# DIGILATL_INPUT.net
KiCad netlist of a schematic drawn in Altium Designer
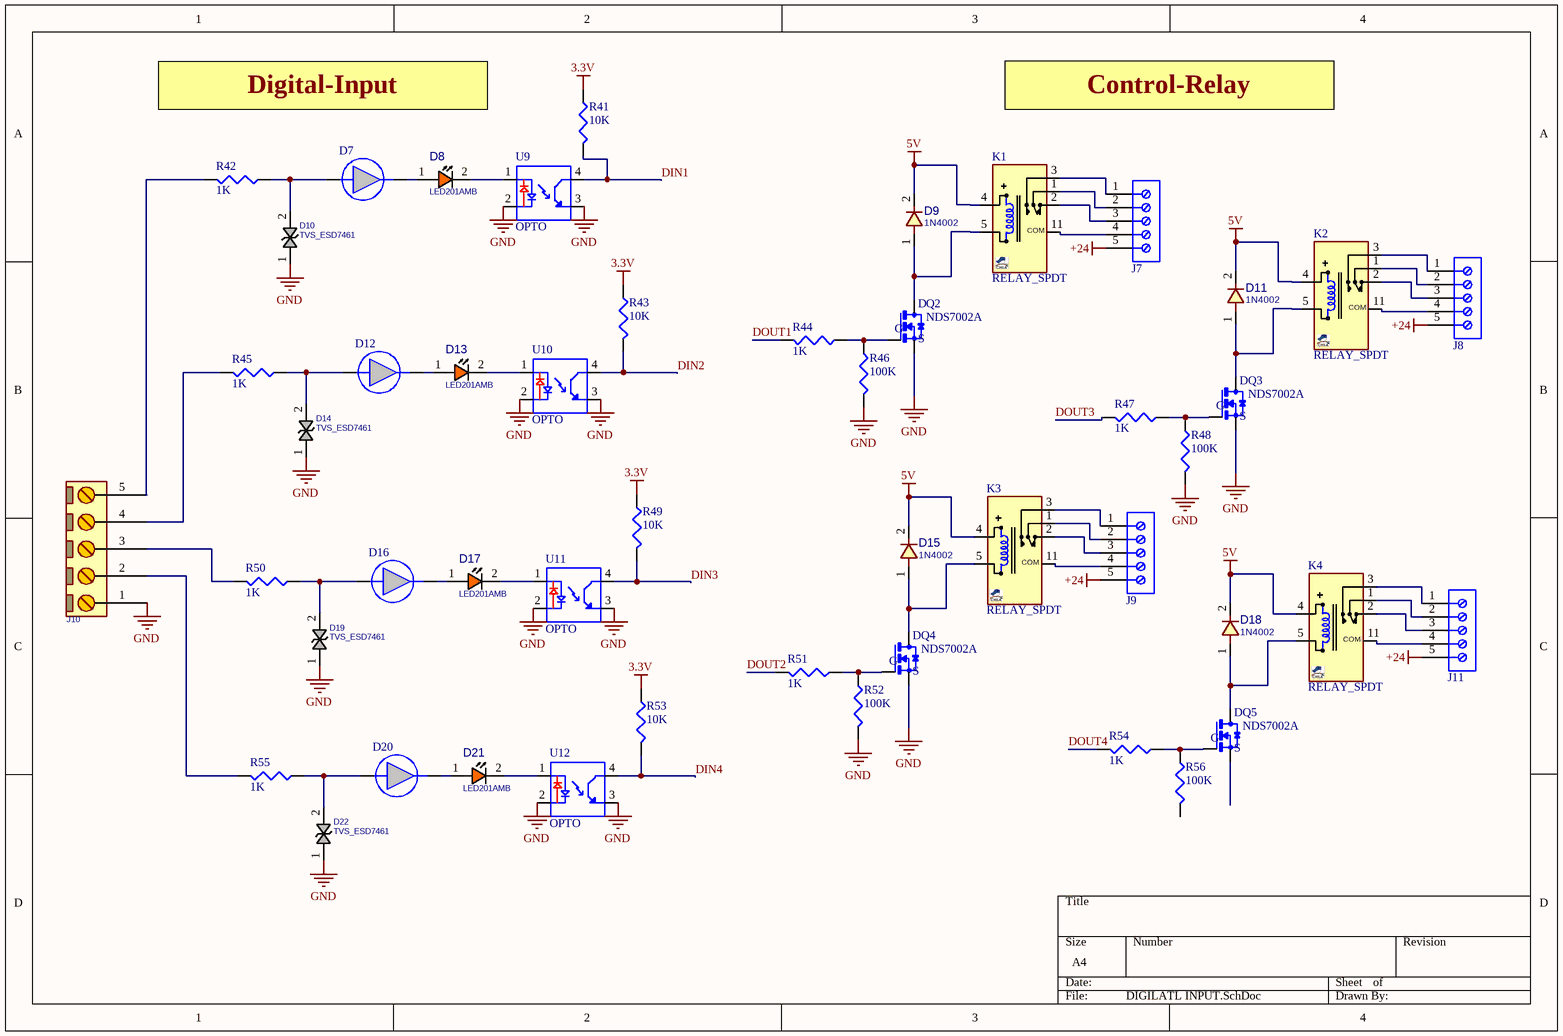
[diagram p0: DIGILATL INPUT.SchDoc]

(export (version "E")
  (design (tool "Eeschema 10.0.6"))
  (components
    (comp (ref "D7")
      (value "NSI50010YT1G")
      (footprint "DRIVER-LED")
      (description "Constant Current Regulator")
      (fields (field (name "MOUSER PART NUMBER") "863-NSI50010YT1G"))
      (libsource (lib "lib-hiony") (part "DRIVE-LED"))
    )
    (comp (ref "D8")
      (value "LED201AMB")
      (footprint "LED0201AMB")
      (description "LED, SMD, 0201, AMBER")
      (fields (field (name "MANF") "Kingbright") (field (name "MANF_P#") "APG0603SEC-TT"))
      (libsource (lib "led(diode)") (part "LED_SMD_0201_AMB"))
    )
    (comp (ref "D9")
      (value "1N4002")
      (footprint "D_SMA")
      (description "DIODE, GENERAL PURPOSE, 100V/1A")
      (fields (field (name "MANF") "MANF"))
      (libsource (lib "diode") (part "DIODE_SMD_1N4002"))
    )
    (comp (ref "D10")
      (value "TVS_ESD7461")
      (footprint "ESD_XDFN2")
      (description "TVS, ESD PROTECT, Bidirectional")
      (fields (field (name "MANF_P#") "ESD7461N2T5G") (field (name "MANF") "ON"))
      (libsource (lib "protect_tvs_esd_fuse") (part "TVS_ESD7461"))
    )
    (comp (ref "D11")
      (value "1N4002")
      (footprint "D_SMA")
      (description "DIODE, GENERAL PURPOSE, 100V/1A")
      (fields (field (name "MANF") "MANF"))
      (libsource (lib "diode") (part "DIODE_SMD_1N4002"))
    )
    (comp (ref "D12")
      (value "NSI50010YT1G")
      (footprint "DRIVER-LED")
      (description "Constant Current Regulator")
      (fields (field (name "MOUSER PART NUMBER") "863-NSI50010YT1G"))
      (libsource (lib "lib-hiony") (part "DRIVE-LED"))
    )
    (comp (ref "D13")
      (value "LED201AMB")
      (footprint "LED0201AMB")
      (description "LED, SMD, 0201, AMBER")
      (fields (field (name "MANF") "Kingbright") (field (name "MANF_P#") "APG0603SEC-TT"))
      (libsource (lib "led(diode)") (part "LED_SMD_0201_AMB"))
    )
    (comp (ref "D14")
      (value "TVS_ESD7461")
      (footprint "ESD_XDFN2")
      (description "TVS, ESD PROTECT, Bidirectional")
      (fields (field (name "MANF_P#") "ESD7461N2T5G") (field (name "MANF") "ON"))
      (libsource (lib "protect_tvs_esd_fuse") (part "TVS_ESD7461"))
    )
    (comp (ref "D15")
      (value "1N4002")
      (footprint "D_SMA")
      (description "DIODE, GENERAL PURPOSE, 100V/1A")
      (fields (field (name "MANF") "MANF"))
      (libsource (lib "diode") (part "DIODE_SMD_1N4002"))
    )
    (comp (ref "D16")
      (value "NSI50010YT1G")
      (footprint "DRIVER-LED")
      (description "Constant Current Regulator")
      (fields (field (name "MOUSER PART NUMBER") "863-NSI50010YT1G"))
      (libsource (lib "lib-hiony") (part "DRIVE-LED"))
    )
    (comp (ref "D17")
      (value "LED201AMB")
      (footprint "LED0201AMB")
      (description "LED, SMD, 0201, AMBER")
      (fields (field (name "MANF") "Kingbright") (field (name "MANF_P#") "APG0603SEC-TT"))
      (libsource (lib "led(diode)") (part "LED_SMD_0201_AMB"))
    )
    (comp (ref "D18")
      (value "1N4002")
      (footprint "D_SMA")
      (description "DIODE, GENERAL PURPOSE, 100V/1A")
      (fields (field (name "MANF") "MANF"))
      (libsource (lib "diode") (part "DIODE_SMD_1N4002"))
    )
    (comp (ref "D19")
      (value "TVS_ESD7461")
      (footprint "ESD_XDFN2")
      (description "TVS, ESD PROTECT, Bidirectional")
      (fields (field (name "MANF_P#") "ESD7461N2T5G") (field (name "MANF") "ON"))
      (libsource (lib "protect_tvs_esd_fuse") (part "TVS_ESD7461"))
    )
    (comp (ref "D20")
      (value "NSI50010YT1G")
      (footprint "DRIVER-LED")
      (description "Constant Current Regulator")
      (fields (field (name "MOUSER PART NUMBER") "863-NSI50010YT1G"))
      (libsource (lib "lib-hiony") (part "DRIVE-LED"))
    )
    (comp (ref "D21")
      (value "LED201AMB")
      (footprint "LED0201AMB")
      (description "LED, SMD, 0201, AMBER")
      (fields (field (name "MANF") "Kingbright") (field (name "MANF_P#") "APG0603SEC-TT"))
      (libsource (lib "led(diode)") (part "LED_SMD_0201_AMB"))
    )
    (comp (ref "D22")
      (value "TVS_ESD7461")
      (footprint "ESD_XDFN2")
      (description "TVS, ESD PROTECT, Bidirectional")
      (fields (field (name "MANF_P#") "ESD7461N2T5G") (field (name "MANF") "ON"))
      (libsource (lib "protect_tvs_esd_fuse") (part "TVS_ESD7461"))
    )
    (comp (ref "J7")
      (value "691137710005")
      (footprint "CONN-RELAY")
      (description "WR-TBL Series 1377 Horizontal Entry, THT, pitch 5mm, 5p")
      (fields (field (name "MANUFACTURER") "Wurth Elektronik"))
      (libsource (lib "") (part "CONN-RELAY_1"))
    )
    (comp (ref "J8")
      (value "691137710005")
      (footprint "CONN-RELAY")
      (description "WR-TBL Series 1377 Horizontal Entry, THT, pitch 5mm, 5p")
      (fields (field (name "MANUFACTURER") "Wurth Elektronik"))
      (libsource (lib "lib-hiony") (part "CONN-RELAY"))
    )
    (comp (ref "J9")
      (value "691137710005")
      (footprint "CONN-RELAY")
      (description "WR-TBL Series 1377 Horizontal Entry, THT, pitch 5mm, 5p")
      (fields (field (name "MANUFACTURER") "Wurth Elektronik"))
      (libsource (lib "") (part "CONN-RELAY_1"))
    )
    (comp (ref "J10")
      (value "CONN_TB5")
      (footprint "MSTB_5")
      (description "CONN, PHOENIX MSTB, 5-G, 5.08mm pitch")
      (libsource (lib "conn_power_terminalB") (part "CONN_MSTB_5"))
    )
    (comp (ref "J11")
      (value "691137710005")
      (footprint "CONN-RELAY")
      (description "WR-TBL Series 1377 Horizontal Entry, THT, pitch 5mm, 5p")
      (fields (field (name "MANUFACTURER") "Wurth Elektronik"))
      (libsource (lib "lib-hiony") (part "CONN-RELAY"))
    )
    (comp (ref "K1")
      (value "RELAY_SPDT")
      (footprint "REL_SPDT_6_1611")
      (description "Relay, SPDT, 5P, 15.5X11mm, TRB 125VAC/1A")
      (fields (field (name "MANF") "TTI") (field (name "MANF_P#") "TRB-12VDC-A"))
      (libsource (lib "relay") (part "RELAY_SPDT_6_1611_TRB"))
    )
    (comp (ref "K2")
      (value "RELAY_SPDT")
      (footprint "REL_SPDT_6_1611")
      (description "Relay, SPDT, 5P, 15.5X11mm, TRB 125VAC/1A")
      (fields (field (name "MANF") "TTI") (field (name "MANF_P#") "TRB-12VDC-A"))
      (libsource (lib "relay") (part "RELAY_SPDT_6_1611_TRB"))
    )
    (comp (ref "K3")
      (value "RELAY_SPDT")
      (footprint "REL_SPDT_6_1611")
      (description "Relay, SPDT, 5P, 15.5X11mm, TRB 125VAC/1A")
      (fields (field (name "MANF") "TTI") (field (name "MANF_P#") "TRB-12VDC-A"))
      (libsource (lib "relay") (part "RELAY_SPDT_6_1611_TRB"))
    )
    (comp (ref "K4")
      (value "RELAY_SPDT")
      (footprint "REL_SPDT_6_1611")
      (description "Relay, SPDT, 5P, 15.5X11mm, TRB 125VAC/1A")
      (fields (field (name "MANF") "TTI") (field (name "MANF_P#") "TRB-12VDC-A"))
      (libsource (lib "relay") (part "RELAY_SPDT_6_1611_TRB"))
    )
    (comp (ref "Q2")
      (value "NDS7002A")
      (footprint "SOT23")
      (description "NDS Series N-Channel 60 V 2 Ohm Enhancement Mode Field Effect Transistor SOT-23")
      (fields (field (name "MF") "ON Semiconductor"))
      (libsource (lib "lib-hiony") (part "NDS7002A"))
    )
    (comp (ref "Q3")
      (value "NDS7002A")
      (footprint "SOT23")
      (description "NDS Series N-Channel 60 V 2 Ohm Enhancement Mode Field Effect Transistor SOT-23")
      (fields (field (name "MF") "ON Semiconductor"))
      (libsource (lib "lib-hiony") (part "NDS7002A"))
    )
    (comp (ref "Q4")
      (value "NDS7002A")
      (footprint "SOT23")
      (description "NDS Series N-Channel 60 V 2 Ohm Enhancement Mode Field Effect Transistor SOT-23")
      (fields (field (name "MF") "ON Semiconductor"))
      (libsource (lib "lib-hiony") (part "NDS7002A"))
    )
    (comp (ref "Q5")
      (value "NDS7002A")
      (footprint "SOT23")
      (description "NDS Series N-Channel 60 V 2 Ohm Enhancement Mode Field Effect Transistor SOT-23")
      (fields (field (name "MF") "ON Semiconductor"))
      (libsource (lib "lib-hiony") (part "NDS7002A"))
    )
    (comp (ref "R41")
      (value "10K")
      (footprint "0603L")
      (description "RES SMD 10K OHM 1% 1/10W 0603")
      (fields
        (field (name "DIGI-KEY PART NUMBER") "1276-3485-1-ND")
        (field (name "MANUFACTURER PART NUMBER") "RC1608F103CS")
      )
      (libsource (lib "Miscellaneous Devices") (part "Res3"))
    )
    (comp (ref "R42")
      (value "1K")
      (footprint "0603L")
      (description "RES SMD 1K OHM 1% 1/10W 0603")
      (fields
        (field (name "DIGI-KEY PART NUMBER") "1276-3484-1-ND")
        (field (name "MANUFACTURER PART NUMBER") "RC1608F102CS")
        (field (name "PUBLISHER") "Altium Limited")
      )
      (libsource (lib "Miscellaneous Devices") (part "Res3"))
    )
    (comp (ref "R43")
      (value "10K")
      (footprint "0603L")
      (description "RES SMD 10K OHM 1% 1/10W 0603")
      (fields
        (field (name "DIGI-KEY PART NUMBER") "1276-3485-1-ND")
        (field (name "MANUFACTURER PART NUMBER") "RC1608F103CS")
      )
      (libsource (lib "Miscellaneous Devices") (part "Res3"))
    )
    (comp (ref "R44")
      (value "1K")
      (footprint "0603L")
      (description "RES SMD 1K OHM 1% 1/10W 0603")
      (fields
        (field (name "DIGI-KEY PART NUMBER") "1276-3484-1-ND")
        (field (name "MANUFACTURER PART NUMBER") "RC1608F102CS")
        (field (name "PUBLISHER") "Altium Limited")
      )
      (libsource (lib "Miscellaneous Devices") (part "Res3"))
    )
    (comp (ref "R45")
      (value "1K")
      (footprint "0603L")
      (description "RES SMD 1K OHM 1% 1/10W 0603")
      (fields
        (field (name "DIGI-KEY PART NUMBER") "1276-3484-1-ND")
        (field (name "MANUFACTURER PART NUMBER") "RC1608F102CS")
        (field (name "PUBLISHER") "Altium Limited")
      )
      (libsource (lib "Miscellaneous Devices") (part "Res3"))
    )
    (comp (ref "R46")
      (value "100K")
      (footprint "0603L")
      (description "RES SMD 1K OHM 1% 1/10W 0603")
      (fields
        (field (name "DIGI-KEY PART NUMBER") "1276-3484-1-ND")
        (field (name "MANUFACTURER PART NUMBER") "RC1608F102CS")
        (field (name "PUBLISHER") "Altium Limited")
      )
      (libsource (lib "Miscellaneous Devices") (part "Res3"))
    )
    (comp (ref "R47")
      (value "1K")
      (footprint "0603L")
      (description "RES SMD 1K OHM 1% 1/10W 0603")
      (fields
        (field (name "DIGI-KEY PART NUMBER") "1276-3484-1-ND")
        (field (name "MANUFACTURER PART NUMBER") "RC1608F102CS")
        (field (name "PUBLISHER") "Altium Limited")
      )
      (libsource (lib "Miscellaneous Devices") (part "Res3"))
    )
    (comp (ref "R48")
      (value "100K")
      (footprint "0603L")
      (description "RES SMD 1K OHM 1% 1/10W 0603")
      (fields
        (field (name "DIGI-KEY PART NUMBER") "1276-3484-1-ND")
        (field (name "MANUFACTURER PART NUMBER") "RC1608F102CS")
        (field (name "PUBLISHER") "Altium Limited")
      )
      (libsource (lib "Miscellaneous Devices") (part "Res3"))
    )
    (comp (ref "R49")
      (value "10K")
      (footprint "0603L")
      (description "RES SMD 10K OHM 1% 1/10W 0603")
      (fields
        (field (name "DIGI-KEY PART NUMBER") "1276-3485-1-ND")
        (field (name "MANUFACTURER PART NUMBER") "RC1608F103CS")
      )
      (libsource (lib "Miscellaneous Devices") (part "Res3"))
    )
    (comp (ref "R50")
      (value "1K")
      (footprint "0603L")
      (description "RES SMD 1K OHM 1% 1/10W 0603")
      (fields
        (field (name "DIGI-KEY PART NUMBER") "1276-3484-1-ND")
        (field (name "MANUFACTURER PART NUMBER") "RC1608F102CS")
        (field (name "PUBLISHER") "Altium Limited")
      )
      (libsource (lib "Miscellaneous Devices") (part "Res3"))
    )
    (comp (ref "R51")
      (value "1K")
      (footprint "0603L")
      (description "RES SMD 1K OHM 1% 1/10W 0603")
      (fields
        (field (name "DIGI-KEY PART NUMBER") "1276-3484-1-ND")
        (field (name "MANUFACTURER PART NUMBER") "RC1608F102CS")
        (field (name "PUBLISHER") "Altium Limited")
      )
      (libsource (lib "Miscellaneous Devices") (part "Res3"))
    )
    (comp (ref "R52")
      (value "100K")
      (footprint "0603L")
      (description "RES SMD 1K OHM 1% 1/10W 0603")
      (fields
        (field (name "DIGI-KEY PART NUMBER") "1276-3484-1-ND")
        (field (name "MANUFACTURER PART NUMBER") "RC1608F102CS")
        (field (name "PUBLISHER") "Altium Limited")
      )
      (libsource (lib "Miscellaneous Devices") (part "Res3"))
    )
    (comp (ref "R53")
      (value "10K")
      (footprint "0603L")
      (description "RES SMD 10K OHM 1% 1/10W 0603")
      (fields
        (field (name "DIGI-KEY PART NUMBER") "1276-3485-1-ND")
        (field (name "MANUFACTURER PART NUMBER") "RC1608F103CS")
      )
      (libsource (lib "Miscellaneous Devices") (part "Res3"))
    )
    (comp (ref "R54")
      (value "1K")
      (footprint "0603L")
      (description "RES SMD 1K OHM 1% 1/10W 0603")
      (fields
        (field (name "DIGI-KEY PART NUMBER") "1276-3484-1-ND")
        (field (name "MANUFACTURER PART NUMBER") "RC1608F102CS")
        (field (name "PUBLISHER") "Altium Limited")
      )
      (libsource (lib "Miscellaneous Devices") (part "Res3"))
    )
    (comp (ref "R55")
      (value "1K")
      (footprint "0603L")
      (description "RES SMD 1K OHM 1% 1/10W 0603")
      (fields
        (field (name "DIGI-KEY PART NUMBER") "1276-3484-1-ND")
        (field (name "MANUFACTURER PART NUMBER") "RC1608F102CS")
        (field (name "PUBLISHER") "Altium Limited")
      )
      (libsource (lib "Miscellaneous Devices") (part "Res3"))
    )
    (comp (ref "R56")
      (value "100K")
      (footprint "0603L")
      (description "RES SMD 1K OHM 1% 1/10W 0603")
      (fields
        (field (name "DIGI-KEY PART NUMBER") "1276-3484-1-ND")
        (field (name "MANUFACTURER PART NUMBER") "RC1608F102CS")
        (field (name "PUBLISHER") "Altium Limited")
      )
      (libsource (lib "Miscellaneous Devices") (part "Res3"))
    )
    (comp (ref "U9")
      (value "OPTO")
      (footprint "SO_4")
      (description "Optoisolator Transistor Output 3750Vrms 1 Channel 4-SOP")
      (fields (field (name "DIGI-KEY_PART_NUMBER") "TCMT1100CT-ND") (field (name "MP") "TCMT1100"))
      (libsource (lib "lib-hiony") (part "OPTO"))
    )
    (comp (ref "U10")
      (value "OPTO")
      (footprint "SO_4")
      (description "Optoisolator Transistor Output 3750Vrms 1 Channel 4-SOP")
      (fields (field (name "DIGI-KEY_PART_NUMBER") "TCMT1100CT-ND") (field (name "MP") "TCMT1100"))
      (libsource (lib "lib-hiony") (part "OPTO"))
    )
    (comp (ref "U11")
      (value "OPTO")
      (footprint "SO_4")
      (description "Optoisolator Transistor Output 3750Vrms 1 Channel 4-SOP")
      (fields (field (name "DIGI-KEY_PART_NUMBER") "TCMT1100CT-ND") (field (name "MP") "TCMT1100"))
      (libsource (lib "lib-hiony") (part "OPTO"))
    )
    (comp (ref "U12")
      (value "OPTO")
      (footprint "SO_4")
      (description "Optoisolator Transistor Output 3750Vrms 1 Channel 4-SOP")
      (fields (field (name "DIGI-KEY_PART_NUMBER") "TCMT1100CT-ND") (field (name "MP") "TCMT1100"))
      (libsource (lib "lib-hiony") (part "OPTO"))
    )
  )
  (nets
    (net (code "1") (name "+24") (class "Default")
      (node (ref "J11") (pin "5") (pinfunction "5_5") (pintype "passive"))
      (node (ref "J7") (pin "5") (pinfunction "5_5") (pintype "passive"))
      (node (ref "J8") (pin "5") (pinfunction "5_5") (pintype "passive"))
      (node (ref "J9") (pin "5") (pinfunction "5_5") (pintype "passive"))
    )
    (net (code "2") (name "/DIN1") (class "Default")
      (node (ref "R41") (pin "2") (pinfunction "2_2") (pintype "passive"))
      (node (ref "U9") (pin "4") (pinfunction "CT_4") (pintype "passive"))
    )
    (net (code "3") (name "/DIN2") (class "Default")
      (node (ref "R43") (pin "2") (pinfunction "2_2") (pintype "passive"))
      (node (ref "U10") (pin "4") (pinfunction "CT_4") (pintype "passive"))
    )
    (net (code "4") (name "/DIN3") (class "Default")
      (node (ref "R49") (pin "2") (pinfunction "2_2") (pintype "passive"))
      (node (ref "U11") (pin "4") (pinfunction "CT_4") (pintype "passive"))
    )
    (net (code "5") (name "/DIN4") (class "Default")
      (node (ref "R53") (pin "2") (pinfunction "2_2") (pintype "passive"))
      (node (ref "U12") (pin "4") (pinfunction "CT_4") (pintype "passive"))
    )
    (net (code "6") (name "/DOUT1") (class "Default")
      (node (ref "R44") (pin "2") (pinfunction "2_2") (pintype "passive"))
    )
    (net (code "7") (name "/DOUT2") (class "Default")
      (node (ref "R51") (pin "2") (pinfunction "2_2") (pintype "passive"))
    )
    (net (code "8") (name "/DOUT3") (class "Default")
      (node (ref "R47") (pin "2") (pinfunction "2_2") (pintype "passive"))
    )
    (net (code "9") (name "/DOUT4") (class "Default")
      (node (ref "R54") (pin "2") (pinfunction "2_2") (pintype "passive"))
    )
    (net (code "10") (name "3.3V") (class "Default")
      (node (ref "R41") (pin "1") (pinfunction "1_1") (pintype "passive"))
      (node (ref "R43") (pin "1") (pinfunction "1_1") (pintype "passive"))
      (node (ref "R49") (pin "1") (pinfunction "1_1") (pintype "passive"))
      (node (ref "R53") (pin "1") (pinfunction "1_1") (pintype "passive"))
    )
    (net (code "11") (name "5V") (class "Default")
      (node (ref "D11") (pin "2") (pinfunction "2_2") (pintype "passive"))
      (node (ref "D15") (pin "2") (pinfunction "2_2") (pintype "passive"))
      (node (ref "D18") (pin "2") (pinfunction "2_2") (pintype "passive"))
      (node (ref "D9") (pin "2") (pinfunction "2_2") (pintype "passive"))
      (node (ref "K1") (pin "4") (pinfunction "T1_4") (pintype "passive"))
      (node (ref "K2") (pin "4") (pinfunction "T1_4") (pintype "passive"))
      (node (ref "K3") (pin "4") (pinfunction "T1_4") (pintype "passive"))
      (node (ref "K4") (pin "4") (pinfunction "T1_4") (pintype "passive"))
    )
    (net (code "12") (name "GND") (class "Default")
      (node (ref "D10") (pin "1") (pinfunction "1_1") (pintype "passive"))
      (node (ref "D14") (pin "1") (pinfunction "1_1") (pintype "passive"))
      (node (ref "D19") (pin "1") (pinfunction "1_1") (pintype "passive"))
      (node (ref "D22") (pin "1") (pinfunction "1_1") (pintype "passive"))
      (node (ref "J10") (pin "1") (pinfunction "1_1") (pintype "passive"))
      (node (ref "Q2") (pin "2") (pinfunction "S_2") (pintype "passive"))
      (node (ref "Q3") (pin "2") (pinfunction "S_2") (pintype "passive"))
      (node (ref "Q4") (pin "2") (pinfunction "S_2") (pintype "passive"))
      (node (ref "R46") (pin "2") (pinfunction "2_2") (pintype "passive"))
      (node (ref "R48") (pin "2") (pinfunction "2_2") (pintype "passive"))
      (node (ref "R52") (pin "2") (pinfunction "2_2") (pintype "passive"))
      (node (ref "U10") (pin "2") (pinfunction "C_2") (pintype "passive"))
      (node (ref "U10") (pin "3") (pinfunction "ET_3") (pintype "passive"))
      (node (ref "U11") (pin "2") (pinfunction "C_2") (pintype "passive"))
      (node (ref "U11") (pin "3") (pinfunction "ET_3") (pintype "passive"))
      (node (ref "U12") (pin "2") (pinfunction "C_2") (pintype "passive"))
      (node (ref "U12") (pin "3") (pinfunction "ET_3") (pintype "passive"))
      (node (ref "U9") (pin "2") (pinfunction "C_2") (pintype "passive"))
      (node (ref "U9") (pin "3") (pinfunction "ET_3") (pintype "passive"))
    )
    (net (code "13") (name "Net-(D7-A)") (class "Default")
      (node (ref "D10") (pin "2") (pinfunction "2_2") (pintype "passive"))
      (node (ref "D7") (pin "2") (pinfunction "A_2") (pintype "passive"))
      (node (ref "R42") (pin "1") (pinfunction "1_1") (pintype "passive"))
    )
    (net (code "14") (name "Net-(D7-K)") (class "Default")
      (node (ref "D7") (pin "1") (pinfunction "K_1") (pintype "passive"))
      (node (ref "D8") (pin "1") (pinfunction "ANODE_1") (pintype "passive"))
    )
    (net (code "15") (name "Net-(D8-CATHODE)") (class "Default")
      (node (ref "D8") (pin "2") (pinfunction "CATHODE_2") (pintype "passive"))
      (node (ref "U9") (pin "1") (pinfunction "A_1") (pintype "passive"))
    )
    (net (code "16") (name "Net-(D12-A)") (class "Default")
      (node (ref "D12") (pin "2") (pinfunction "A_2") (pintype "passive"))
      (node (ref "D14") (pin "2") (pinfunction "2_2") (pintype "passive"))
      (node (ref "R45") (pin "1") (pinfunction "1_1") (pintype "passive"))
    )
    (net (code "17") (name "Net-(D12-K)") (class "Default")
      (node (ref "D12") (pin "1") (pinfunction "K_1") (pintype "passive"))
      (node (ref "D13") (pin "1") (pinfunction "ANODE_1") (pintype "passive"))
    )
    (net (code "18") (name "Net-(D13-CATHODE)") (class "Default")
      (node (ref "D13") (pin "2") (pinfunction "CATHODE_2") (pintype "passive"))
      (node (ref "U10") (pin "1") (pinfunction "A_1") (pintype "passive"))
    )
    (net (code "19") (name "Net-(D16-A)") (class "Default")
      (node (ref "D16") (pin "2") (pinfunction "A_2") (pintype "passive"))
      (node (ref "D19") (pin "2") (pinfunction "2_2") (pintype "passive"))
      (node (ref "R50") (pin "1") (pinfunction "1_1") (pintype "passive"))
    )
    (net (code "20") (name "Net-(D16-K)") (class "Default")
      (node (ref "D16") (pin "1") (pinfunction "K_1") (pintype "passive"))
      (node (ref "D17") (pin "1") (pinfunction "ANODE_1") (pintype "passive"))
    )
    (net (code "21") (name "Net-(D17-CATHODE)") (class "Default")
      (node (ref "D17") (pin "2") (pinfunction "CATHODE_2") (pintype "passive"))
      (node (ref "U11") (pin "1") (pinfunction "A_1") (pintype "passive"))
    )
    (net (code "22") (name "Net-(D20-A)") (class "Default")
      (node (ref "D20") (pin "2") (pinfunction "A_2") (pintype "passive"))
      (node (ref "D22") (pin "2") (pinfunction "2_2") (pintype "passive"))
      (node (ref "R55") (pin "1") (pinfunction "1_1") (pintype "passive"))
    )
    (net (code "23") (name "Net-(D20-K)") (class "Default")
      (node (ref "D20") (pin "1") (pinfunction "K_1") (pintype "passive"))
      (node (ref "D21") (pin "1") (pinfunction "ANODE_1") (pintype "passive"))
    )
    (net (code "24") (name "Net-(D21-CATHODE)") (class "Default")
      (node (ref "D21") (pin "2") (pinfunction "CATHODE_2") (pintype "passive"))
      (node (ref "U12") (pin "1") (pinfunction "A_1") (pintype "passive"))
    )
    (net (code "25") (name "Net-(J7-Pad2)") (class "Default")
      (node (ref "J7") (pin "2") (pinfunction "2_2") (pintype "passive"))
      (node (ref "K1") (pin "1") (pinfunction "COM_1") (pintype "passive"))
    )
    (net (code "26") (name "Net-(J7-Pad4)") (class "Default")
      (node (ref "J7") (pin "4") (pinfunction "4_4") (pintype "passive"))
      (node (ref "K1") (pin "11") (pinfunction "COM_11") (pintype "passive"))
    )
    (net (code "27") (name "Net-(J8-Pad2)") (class "Default")
      (node (ref "J8") (pin "2") (pinfunction "2_2") (pintype "passive"))
      (node (ref "K2") (pin "1") (pinfunction "COM_1") (pintype "passive"))
    )
    (net (code "28") (name "Net-(J8-Pad4)") (class "Default")
      (node (ref "J8") (pin "4") (pinfunction "4_4") (pintype "passive"))
      (node (ref "K2") (pin "11") (pinfunction "COM_11") (pintype "passive"))
    )
    (net (code "29") (name "Net-(J9-Pad2)") (class "Default")
      (node (ref "J9") (pin "2") (pinfunction "2_2") (pintype "passive"))
      (node (ref "K3") (pin "1") (pinfunction "COM_1") (pintype "passive"))
    )
    (net (code "30") (name "Net-(J9-Pad4)") (class "Default")
      (node (ref "J9") (pin "4") (pinfunction "4_4") (pintype "passive"))
      (node (ref "K3") (pin "11") (pinfunction "COM_11") (pintype "passive"))
    )
    (net (code "31") (name "Net-(J10-Pad2)") (class "Default")
      (node (ref "J10") (pin "2") (pinfunction "2_2") (pintype "passive"))
      (node (ref "R55") (pin "2") (pinfunction "2_2") (pintype "passive"))
    )
    (net (code "32") (name "Net-(J10-Pad3)") (class "Default")
      (node (ref "J10") (pin "3") (pinfunction "3_3") (pintype "passive"))
      (node (ref "R50") (pin "2") (pinfunction "2_2") (pintype "passive"))
    )
    (net (code "33") (name "Net-(J10-Pad4)") (class "Default")
      (node (ref "J10") (pin "4") (pinfunction "4_4") (pintype "passive"))
      (node (ref "R45") (pin "2") (pinfunction "2_2") (pintype "passive"))
    )
    (net (code "34") (name "Net-(J10-Pad5)") (class "Default")
      (node (ref "J10") (pin "5") (pinfunction "5_5") (pintype "passive"))
      (node (ref "R42") (pin "2") (pinfunction "2_2") (pintype "passive"))
    )
    (net (code "35") (name "Net-(J11-Pad2)") (class "Default")
      (node (ref "J11") (pin "2") (pinfunction "2_2") (pintype "passive"))
      (node (ref "K4") (pin "1") (pinfunction "COM_1") (pintype "passive"))
    )
    (net (code "36") (name "Net-(J11-Pad4)") (class "Default")
      (node (ref "J11") (pin "4") (pinfunction "4_4") (pintype "passive"))
      (node (ref "K4") (pin "11") (pinfunction "COM_11") (pintype "passive"))
    )
    (net (code "37") (name "Net-(K1-NC)") (class "Default")
      (node (ref "J7") (pin "3") (pinfunction "3_3") (pintype "passive"))
      (node (ref "K1") (pin "2") (pinfunction "NC_2") (pintype "passive"))
    )
    (net (code "38") (name "Net-(K1-NO)") (class "Default")
      (node (ref "J7") (pin "1") (pinfunction "1_1") (pintype "passive"))
      (node (ref "K1") (pin "3") (pinfunction "NO_3") (pintype "passive"))
    )
    (net (code "39") (name "Net-(K1-T2)") (class "Default")
      (node (ref "D9") (pin "1") (pinfunction "1_1") (pintype "passive"))
      (node (ref "K1") (pin "5") (pinfunction "T2_5") (pintype "passive"))
      (node (ref "Q2") (pin "3") (pinfunction "D_3") (pintype "passive"))
    )
    (net (code "40") (name "Net-(K2-NC)") (class "Default")
      (node (ref "J8") (pin "3") (pinfunction "3_3") (pintype "passive"))
      (node (ref "K2") (pin "2") (pinfunction "NC_2") (pintype "passive"))
    )
    (net (code "41") (name "Net-(K2-NO)") (class "Default")
      (node (ref "J8") (pin "1") (pinfunction "1_1") (pintype "passive"))
      (node (ref "K2") (pin "3") (pinfunction "NO_3") (pintype "passive"))
    )
    (net (code "42") (name "Net-(K2-T2)") (class "Default")
      (node (ref "D11") (pin "1") (pinfunction "1_1") (pintype "passive"))
      (node (ref "K2") (pin "5") (pinfunction "T2_5") (pintype "passive"))
      (node (ref "Q3") (pin "3") (pinfunction "D_3") (pintype "passive"))
    )
    (net (code "43") (name "Net-(K3-NC)") (class "Default")
      (node (ref "J9") (pin "3") (pinfunction "3_3") (pintype "passive"))
      (node (ref "K3") (pin "2") (pinfunction "NC_2") (pintype "passive"))
    )
    (net (code "44") (name "Net-(K3-NO)") (class "Default")
      (node (ref "J9") (pin "1") (pinfunction "1_1") (pintype "passive"))
      (node (ref "K3") (pin "3") (pinfunction "NO_3") (pintype "passive"))
    )
    (net (code "45") (name "Net-(K3-T2)") (class "Default")
      (node (ref "D15") (pin "1") (pinfunction "1_1") (pintype "passive"))
      (node (ref "K3") (pin "5") (pinfunction "T2_5") (pintype "passive"))
      (node (ref "Q4") (pin "3") (pinfunction "D_3") (pintype "passive"))
    )
    (net (code "46") (name "Net-(K4-NC)") (class "Default")
      (node (ref "J11") (pin "3") (pinfunction "3_3") (pintype "passive"))
      (node (ref "K4") (pin "2") (pinfunction "NC_2") (pintype "passive"))
    )
    (net (code "47") (name "Net-(K4-NO)") (class "Default")
      (node (ref "J11") (pin "1") (pinfunction "1_1") (pintype "passive"))
      (node (ref "K4") (pin "3") (pinfunction "NO_3") (pintype "passive"))
    )
    (net (code "48") (name "Net-(K4-T2)") (class "Default")
      (node (ref "D18") (pin "1") (pinfunction "1_1") (pintype "passive"))
      (node (ref "K4") (pin "5") (pinfunction "T2_5") (pintype "passive"))
      (node (ref "Q5") (pin "3") (pinfunction "D_3") (pintype "passive"))
    )
    (net (code "49") (name "Net-(Q2-G)") (class "Default")
      (node (ref "Q2") (pin "1") (pinfunction "G_1") (pintype "passive"))
      (node (ref "R44") (pin "1") (pinfunction "1_1") (pintype "passive"))
      (node (ref "R46") (pin "1") (pinfunction "1_1") (pintype "passive"))
    )
    (net (code "50") (name "Net-(Q3-G)") (class "Default")
      (node (ref "Q3") (pin "1") (pinfunction "G_1") (pintype "passive"))
      (node (ref "R47") (pin "1") (pinfunction "1_1") (pintype "passive"))
      (node (ref "R48") (pin "1") (pinfunction "1_1") (pintype "passive"))
    )
    (net (code "51") (name "Net-(Q4-G)") (class "Default")
      (node (ref "Q4") (pin "1") (pinfunction "G_1") (pintype "passive"))
      (node (ref "R51") (pin "1") (pinfunction "1_1") (pintype "passive"))
      (node (ref "R52") (pin "1") (pinfunction "1_1") (pintype "passive"))
    )
    (net (code "52") (name "Net-(Q5-G)") (class "Default")
      (node (ref "Q5") (pin "1") (pinfunction "G_1") (pintype "passive"))
      (node (ref "R54") (pin "1") (pinfunction "1_1") (pintype "passive"))
      (node (ref "R56") (pin "1") (pinfunction "1_1") (pintype "passive"))
    )
    (net (code "53") (name "unconnected-(Q5-S-Pad2)") (class "Default")
      (node (ref "Q5") (pin "2") (pinfunction "S_2") (pintype "passive"))
    )
    (net (code "54") (name "unconnected-(R56-Pad2)") (class "Default")
      (node (ref "R56") (pin "2") (pinfunction "2_2") (pintype "passive"))
    )
  )
)
